# Push_counter.net
KiCad netlist of a schematic drawn in Altium Designer
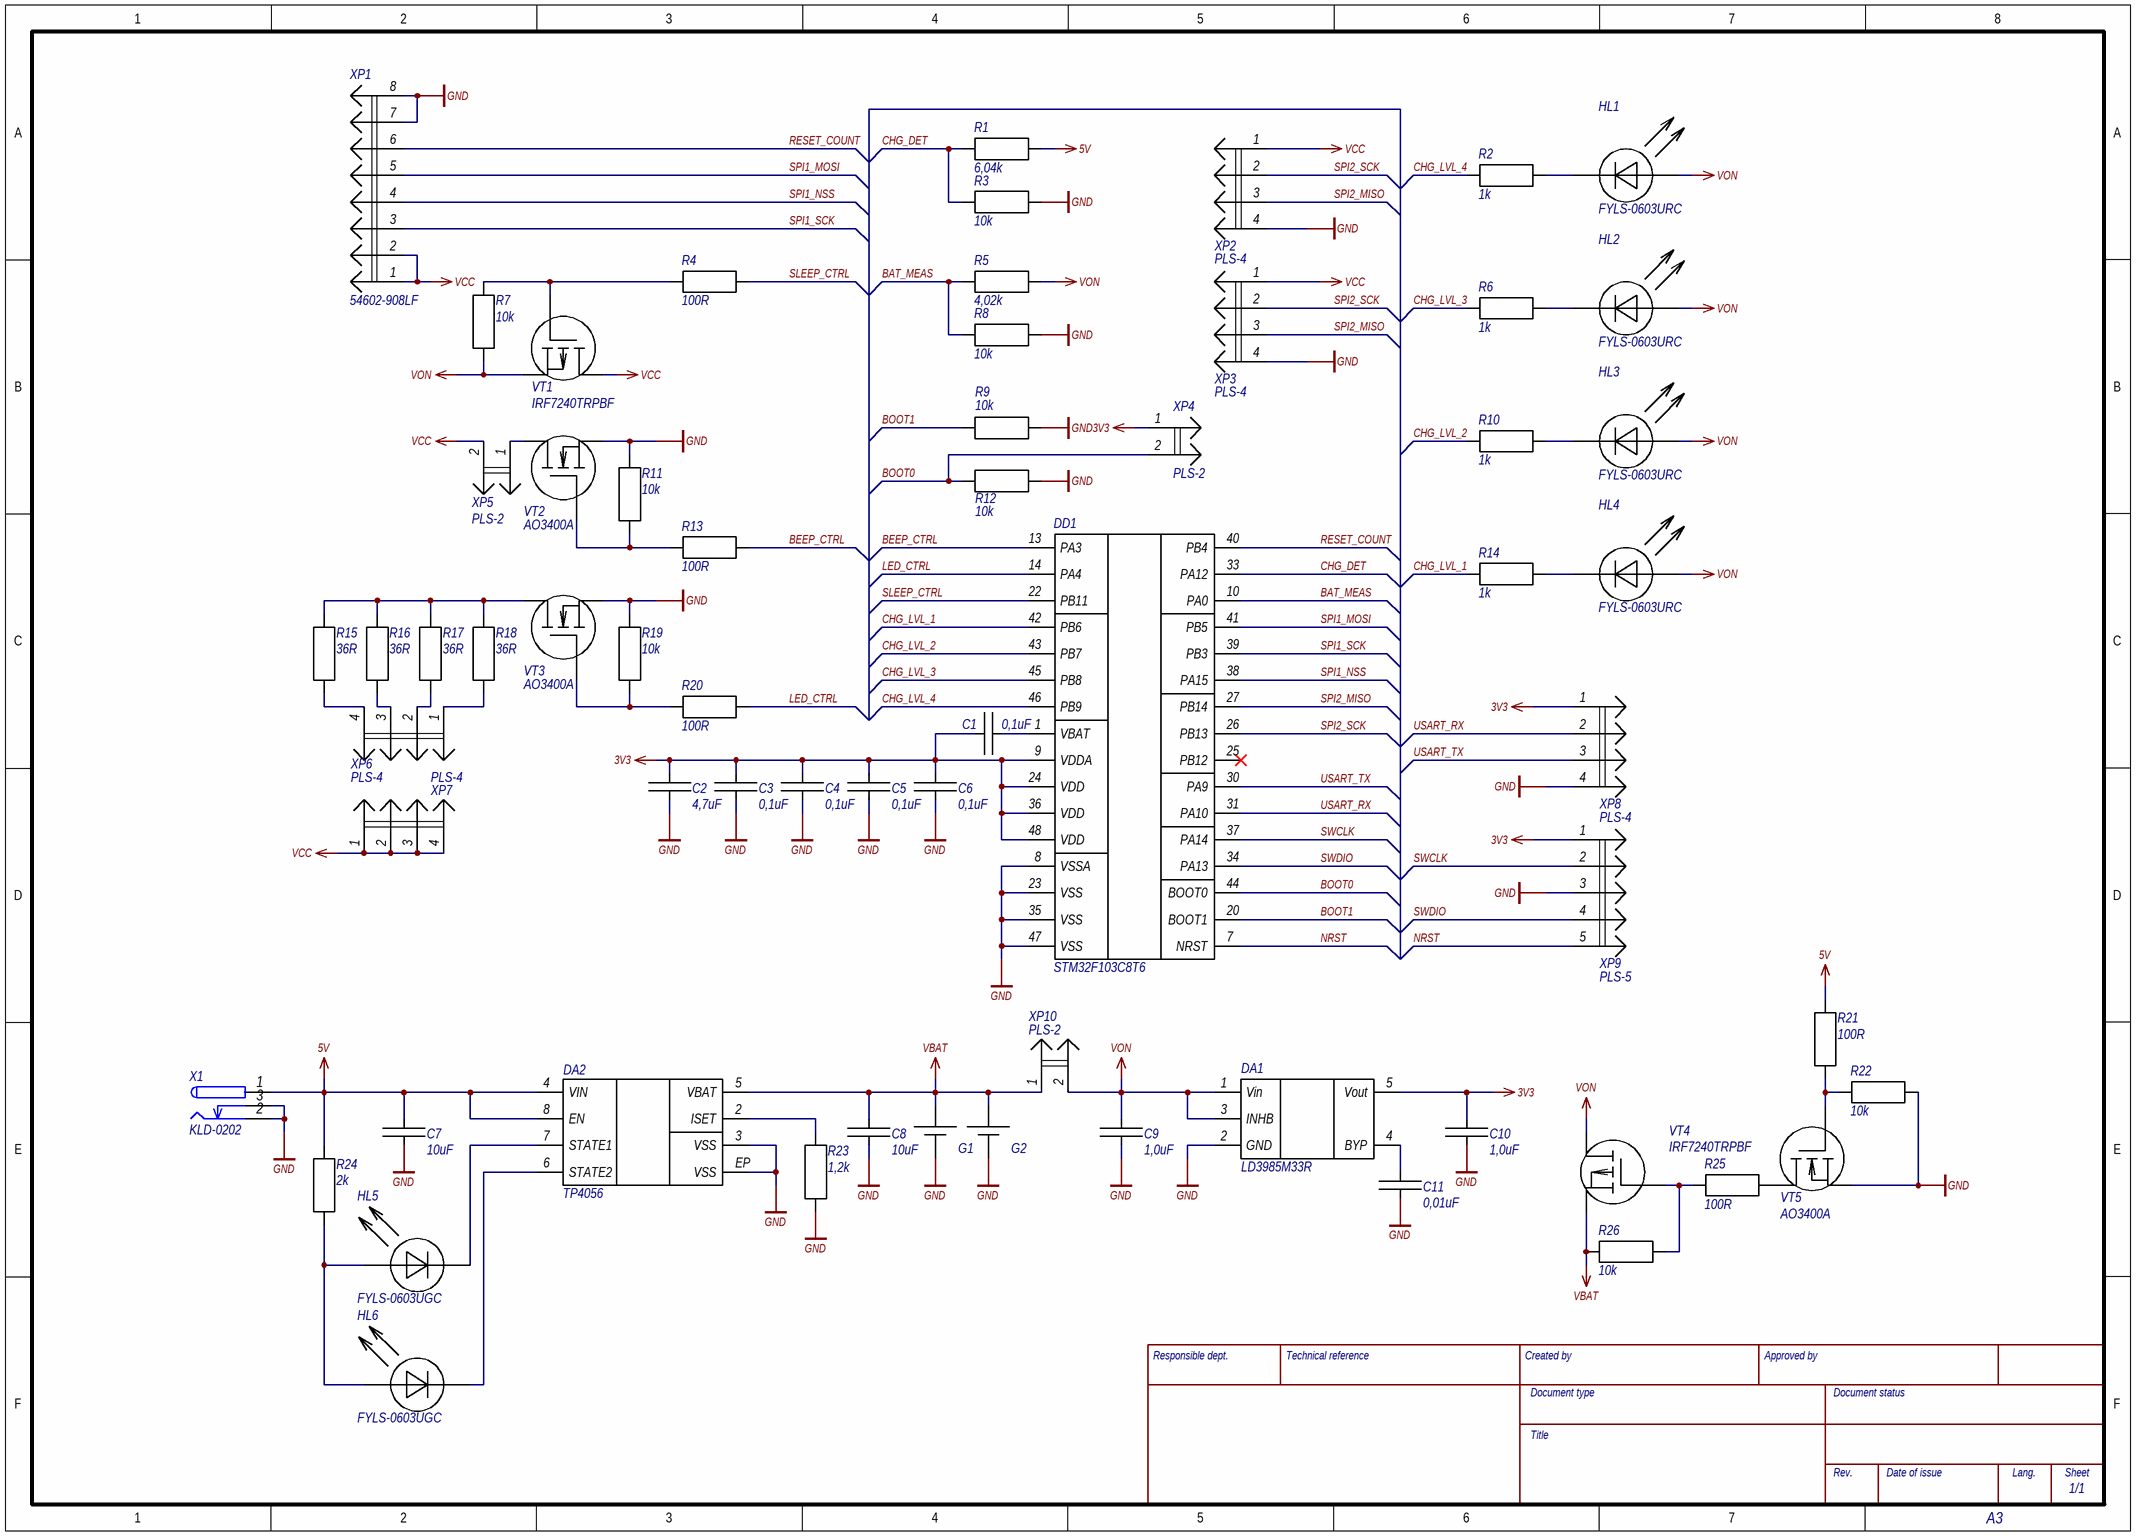
[diagram p0: Push_counter.SchDoc]

(export (version "E")
  (design (tool "Eeschema 10.0.6"))
  (components
    (comp (ref "C1")
      (value "0,1uF")
      (footprint "C0603C")
      (description "C0603C104K5RACAUTO, 0603 X7R  0,1 uF 50V")
      (fields (field (name "PART NUMBER") "C0603C104K5RACAUTO") (field (name "MANUFACTURER") "KEMET"))
      (libsource (lib "lib") (part "Cap"))
    )
    (comp (ref "C2")
      (value "4,7uF")
      (footprint "C0805C")
      (description "CL21B475KOFNFNE, 0805 X7R 4,7 uF 16V")
      (fields (field (name "PART NUMBER") "CL21B475KOFNFNE") (field (name "MANUFACTURER") "Samsung"))
      (libsource (lib "lib") (part "Cap"))
    )
    (comp (ref "C3")
      (value "0,1uF")
      (footprint "C0603C")
      (description "C0603C104K5RACAUTO, 0603 X7R  0,1 uF 50V")
      (fields (field (name "PART NUMBER") "C0603C104K5RACAUTO") (field (name "MANUFACTURER") "KEMET"))
      (libsource (lib "lib") (part "Cap"))
    )
    (comp (ref "C4")
      (value "0,1uF")
      (footprint "C0603C")
      (description "C0603C104K5RACAUTO, 0603 X7R  0,1 uF 50V")
      (fields (field (name "PART NUMBER") "C0603C104K5RACAUTO") (field (name "MANUFACTURER") "KEMET"))
      (libsource (lib "lib") (part "Cap"))
    )
    (comp (ref "C5")
      (value "0,1uF")
      (footprint "C0603C")
      (description "C0603C104K5RACAUTO, 0603 X7R  0,1 uF 50V")
      (fields (field (name "PART NUMBER") "C0603C104K5RACAUTO") (field (name "MANUFACTURER") "KEMET"))
      (libsource (lib "lib") (part "Cap"))
    )
    (comp (ref "C6")
      (value "0,1uF")
      (footprint "C0603C")
      (description "C0603C104K5RACAUTO, 0603 X7R  0,1 uF 50V")
      (fields (field (name "PART NUMBER") "C0603C104K5RACAUTO") (field (name "MANUFACTURER") "KEMET"))
      (libsource (lib "lib") (part "Cap"))
    )
    (comp (ref "C7")
      (value "10uF")
      (footprint "C1210C")
      (description "C3225X7R1H106M250AC, 1210 X7R 10 uF 50V")
      (fields (field (name "PART NUMBER") "C3225X7R1H106M250AC") (field (name "MANUFACTURER") "TDK"))
      (libsource (lib "lib") (part "Cap"))
    )
    (comp (ref "C8")
      (value "10uF")
      (footprint "C1210C")
      (description "C3225X7R1H106M250AC, 1210 X7R 10 uF 50V")
      (fields (field (name "PART NUMBER") "C3225X7R1H106M250AC") (field (name "MANUFACTURER") "TDK"))
      (libsource (lib "lib") (part "Cap"))
    )
    (comp (ref "C9")
      (value "1,0uF")
      (footprint "C0603C")
      (description "CL10B105KA8NNNC, 0603 X7R 1,0 uF 25V")
      (fields (field (name "PART NUMBER") "CL10B105KA8NNNC") (field (name "MANUFACTURER") "Samsung"))
      (libsource (lib "lib") (part "Cap"))
    )
    (comp (ref "C10")
      (value "1,0uF")
      (footprint "C0603C")
      (description "CL10B105KA8NNNC, 0603 X7R 1,0 uF 25V")
      (fields (field (name "PART NUMBER") "CL10B105KA8NNNC") (field (name "MANUFACTURER") "Samsung"))
      (libsource (lib "lib") (part "Cap"))
    )
    (comp (ref "C11")
      (value "0,01uF")
      (footprint "C0603C")
      (description "CL10B103KC8NNNC, 0603 X7R 0,01 uF 100V")
      (fields (field (name "PART NUMBER") "CL10B103KC8NNNC") (field (name "MANUFACTURER") "Samsung"))
      (libsource (lib "lib") (part "Cap"))
    )
    (comp (ref "DA1")
      (value "LD3985M33R")
      (footprint "SOT23-5")
      (description "Linear Voltage Regulator")
      (fields (field (name "MANUFACTURER") "Microchip Technology"))
      (libsource (lib "lib") (part "LD3985M33R"))
    )
    (comp (ref "DA2")
      (value "TP4056")
      (footprint "SO-8-EP")
      (fields (field (name "MANUFACTURER") "UMW"))
      (libsource (lib "lib") (part "TP4056"))
    )
    (comp (ref "DD1")
      (value "STM32F103C8T6")
      (footprint "LQFP48")
      (description "STM32F103C8T6, 64 KB Flash, 20 KB RAM, LQFP48")
      (fields (field (name "MANUFACTURER") "STMicroelectronics"))
      (libsource (lib "lib") (part "STM32F103C8T6"))
    )
    (comp (ref "G1")
      (value "KLS5-18650-L")
      (footprint "KLS5-18650-L")
      (description "KLS5-18650-L, , BAT")
      (libsource (lib "lib") (part "G-ELEM"))
    )
    (comp (ref "G2")
      (value "KLS5-18650-L")
      (footprint "KLS5-18650-L")
      (description "KLS5-18650-L, , BAT")
      (libsource (lib "lib") (part "G-ELEM"))
    )
    (comp (ref "HL1")
      (value "FYLS-0603URC")
      (footprint "LED0603")
      (description "SMD 0603 Red 30mA 80mcd")
      (fields (field (name "MANUFACTURER") "Foryard") (field (name "VOLTAGE") "2.1V"))
      (libsource (lib "lib") (part "LED"))
    )
    (comp (ref "HL2")
      (value "FYLS-0603URC")
      (footprint "LED0603")
      (description "SMD 0603 Red 30mA 80mcd")
      (fields (field (name "MANUFACTURER") "Foryard") (field (name "VOLTAGE") "2.1V"))
      (libsource (lib "lib") (part "LED"))
    )
    (comp (ref "HL3")
      (value "FYLS-0603URC")
      (footprint "LED0603")
      (description "SMD 0603 Red 30mA 80mcd")
      (fields (field (name "MANUFACTURER") "Foryard") (field (name "VOLTAGE") "2.1V"))
      (libsource (lib "lib") (part "LED"))
    )
    (comp (ref "HL4")
      (value "FYLS-0603URC")
      (footprint "LED0603")
      (description "SMD 0603 Red 30mA 80mcd")
      (fields (field (name "MANUFACTURER") "Foryard") (field (name "VOLTAGE") "2.1V"))
      (libsource (lib "lib") (part "LED"))
    )
    (comp (ref "HL5")
      (value "FYLS-0603UGC")
      (footprint "LED0603")
      (description "SMD 0603 Green 30mA 65mcd")
      (fields (field (name "MANUFACTURER") "Foryard") (field (name "VOLTAGE") "2V"))
      (libsource (lib "lib") (part "LED"))
    )
    (comp (ref "HL6")
      (value "FYLS-0603UGC")
      (footprint "LED0603")
      (description "SMD 0603 Green 30mA 65mcd")
      (fields (field (name "MANUFACTURER") "Foryard") (field (name "VOLTAGE") "2V"))
      (libsource (lib "lib") (part "LED"))
    )
    (comp (ref "R1")
      (value "6,04k")
      (footprint "C0603R")
      (description "RC0603FR-076K04L, 1% 6,04k")
      (fields (field (name "PART NUMBER") "RC0603FR-076K04L") (field (name "MANUFACTURER") "Yageo"))
      (libsource (lib "lib") (part "res"))
    )
    (comp (ref "R2")
      (value "1k")
      (footprint "C0603R")
      (description "RC0603JR-071KL, 5% 1k")
      (fields (field (name "PART NUMBER") "RC0603JR-071KL") (field (name "MANUFACTURER") "Yageo"))
      (libsource (lib "lib") (part "res"))
    )
    (comp (ref "R3")
      (value "10k")
      (footprint "C0603R")
      (description "RC0603FR-0710KL, 1% 10k")
      (fields (field (name "PART NUMBER") "RC0603FR-0710KL") (field (name "MANUFACTURER") "Yageo"))
      (libsource (lib "lib") (part "res"))
    )
    (comp (ref "R4")
      (value "100R")
      (footprint "C0603R")
      (description "RC0603FR-07100RL, 1% 100R")
      (fields (field (name "PART NUMBER") "RC0603FR-07100RL") (field (name "MANUFACTURER") "Yageo"))
      (libsource (lib "lib") (part "res"))
    )
    (comp (ref "R5")
      (value "4,02k")
      (footprint "C0603R")
      (description "RC0603FR-074K02L, 1% 4,02k")
      (fields (field (name "PART NUMBER") "RC0603FR-074K02L") (field (name "MANUFACTURER") "Yageo"))
      (libsource (lib "lib") (part "res"))
    )
    (comp (ref "R6")
      (value "1k")
      (footprint "C0603R")
      (description "RC0603JR-071KL, 5% 1k")
      (fields (field (name "PART NUMBER") "RC0603JR-071KL") (field (name "MANUFACTURER") "Yageo"))
      (libsource (lib "lib") (part "res"))
    )
    (comp (ref "R7")
      (value "10k")
      (footprint "C0603R")
      (description "RC0603JR-0710KL, 5% 10k")
      (fields (field (name "PART NUMBER") "RC0603JR-0710KL") (field (name "MANUFACTURER") "Yageo"))
      (libsource (lib "lib") (part "res"))
    )
    (comp (ref "R8")
      (value "10k")
      (footprint "C0603R")
      (description "RC0603FR-0710KL, 1% 10k")
      (fields (field (name "PART NUMBER") "RC0603FR-0710KL") (field (name "MANUFACTURER") "Yageo"))
      (libsource (lib "lib") (part "res"))
    )
    (comp (ref "R9")
      (value "10k")
      (footprint "C0603R")
      (description "RC0603JR-0710KL, 5% 10k")
      (fields (field (name "PART NUMBER") "RC0603JR-0710KL") (field (name "MANUFACTURER") "Yageo"))
      (libsource (lib "lib") (part "res"))
    )
    (comp (ref "R10")
      (value "1k")
      (footprint "C0603R")
      (description "RC0603JR-071KL, 5% 1k")
      (fields (field (name "PART NUMBER") "RC0603JR-071KL") (field (name "MANUFACTURER") "Yageo"))
      (libsource (lib "lib") (part "res"))
    )
    (comp (ref "R11")
      (value "10k")
      (footprint "C0603R")
      (description "RC0603JR-0710KL, 5% 10k")
      (fields (field (name "PART NUMBER") "RC0603JR-0710KL") (field (name "MANUFACTURER") "Yageo"))
      (libsource (lib "lib") (part "res"))
    )
    (comp (ref "R12")
      (value "10k")
      (footprint "C0603R")
      (description "RC0603JR-0710KL, 5% 10k")
      (fields (field (name "PART NUMBER") "RC0603JR-0710KL") (field (name "MANUFACTURER") "Yageo"))
      (libsource (lib "lib") (part "res"))
    )
    (comp (ref "R13")
      (value "100R")
      (footprint "C0603R")
      (description "RC0603FR-07100RL, 1% 100R")
      (fields (field (name "PART NUMBER") "RC0603FR-07100RL") (field (name "MANUFACTURER") "Yageo"))
      (libsource (lib "lib") (part "res"))
    )
    (comp (ref "R14")
      (value "1k")
      (footprint "C0603R")
      (description "RC0603JR-071KL, 5% 1k")
      (fields (field (name "PART NUMBER") "RC0603JR-071KL") (field (name "MANUFACTURER") "Yageo"))
      (libsource (lib "lib") (part "res"))
    )
    (comp (ref "R15")
      (value "36R")
      (footprint "C1206R")
      (description "RC1206JR-0736RL, 5% 36R")
      (fields (field (name "PART NUMBER") "RC1206JR-0736RL") (field (name "MANUFACTURER") "Yageo"))
      (libsource (lib "lib") (part "res"))
    )
    (comp (ref "R16")
      (value "36R")
      (footprint "C1206R")
      (description "RC1206JR-0736RL, 5% 36R")
      (fields (field (name "PART NUMBER") "RC1206JR-0736RL") (field (name "MANUFACTURER") "Yageo"))
      (libsource (lib "lib") (part "res"))
    )
    (comp (ref "R17")
      (value "36R")
      (footprint "C1206R")
      (description "RC1206JR-0736RL, 5% 36R")
      (fields (field (name "PART NUMBER") "RC1206JR-0736RL") (field (name "MANUFACTURER") "Yageo"))
      (libsource (lib "lib") (part "res"))
    )
    (comp (ref "R18")
      (value "36R")
      (footprint "C1206R")
      (description "RC1206JR-0736RL, 5% 36R")
      (fields (field (name "PART NUMBER") "RC1206JR-0736RL") (field (name "MANUFACTURER") "Yageo"))
      (libsource (lib "lib") (part "res"))
    )
    (comp (ref "R19")
      (value "10k")
      (footprint "C0603R")
      (description "RC0603JR-0710KL, 5% 10k")
      (fields (field (name "PART NUMBER") "RC0603JR-0710KL") (field (name "MANUFACTURER") "Yageo"))
      (libsource (lib "lib") (part "res"))
    )
    (comp (ref "R20")
      (value "100R")
      (footprint "C0603R")
      (description "RC0603FR-07100RL, 1% 100R")
      (fields (field (name "PART NUMBER") "RC0603FR-07100RL") (field (name "MANUFACTURER") "Yageo"))
      (libsource (lib "lib") (part "res"))
    )
    (comp (ref "R21")
      (value "100R")
      (footprint "C0603R")
      (description "RC0603FR-07100RL, 1% 100R")
      (fields (field (name "PART NUMBER") "RC0603FR-07100RL") (field (name "MANUFACTURER") "Yageo"))
      (libsource (lib "lib") (part "res"))
    )
    (comp (ref "R22")
      (value "10k")
      (footprint "C0603R")
      (description "RC0603JR-0710KL, 5% 10k")
      (fields (field (name "PART NUMBER") "RC0603JR-0710KL") (field (name "MANUFACTURER") "Yageo"))
      (libsource (lib "lib") (part "res"))
    )
    (comp (ref "R23")
      (value "1,2k")
      (footprint "C0603R")
      (description "RC0603JR-071K2L, 5% 1,2k")
      (fields (field (name "PART NUMBER") "RC0603JR-071K2L") (field (name "MANUFACTURER") "Yageo"))
      (libsource (lib "lib") (part "res"))
    )
    (comp (ref "R24")
      (value "2k")
      (footprint "C0603R")
      (description "RC0603JR-072KL, 5% 2k")
      (fields (field (name "PART NUMBER") "RC0603JR-072KL") (field (name "MANUFACTURER") "Yageo"))
      (libsource (lib "lib") (part "res"))
    )
    (comp (ref "R25")
      (value "100R")
      (footprint "C0603R")
      (description "RC0603FR-07100RL, 1% 100R")
      (fields (field (name "PART NUMBER") "RC0603FR-07100RL") (field (name "MANUFACTURER") "Yageo"))
      (libsource (lib "lib") (part "res"))
    )
    (comp (ref "R26")
      (value "10k")
      (footprint "C0603R")
      (description "RC0603JR-0710KL, 5% 10k")
      (fields (field (name "PART NUMBER") "RC0603JR-0710KL") (field (name "MANUFACTURER") "Yageo"))
      (libsource (lib "lib") (part "res"))
    )
    (comp (ref "VT1")
      (value "IRF7240TRPBF")
      (footprint "SO-8-SINGLE-FET")
      (description "IRF7240TRPBF, SO-8 A V")
      (fields (field (name "MANUFACTURER") "Infineon"))
      (libsource (lib "lib") (part "TRANS-P-FET"))
    )
    (comp (ref "VT2")
      (value "AO3400A")
      (footprint "SOT23-3-FET")
      (description "AO3400A, SOT23-3 5A 30V")
      (fields (field (name "MANUFACTURER") "UMW"))
      (libsource (lib "lib") (part "TRANS-N-FET"))
    )
    (comp (ref "VT3")
      (value "AO3400A")
      (footprint "SOT23-3-FET")
      (description "AO3400A, SOT23-3 5A 30V")
      (fields (field (name "MANUFACTURER") "UMW"))
      (libsource (lib "lib") (part "TRANS-N-FET"))
    )
    (comp (ref "VT4")
      (value "IRF7240TRPBF")
      (footprint "SO-8-SINGLE-FET")
      (description "IRF7240TRPBF, SO-8 A V")
      (fields (field (name "MANUFACTURER") "Infineon"))
      (libsource (lib "lib") (part "TRANS-P-FET"))
    )
    (comp (ref "VT5")
      (value "AO3400A")
      (footprint "SOT23-3-FET")
      (description "AO3400A, SOT23-3 5A 30V")
      (fields (field (name "MANUFACTURER") "UMW"))
      (libsource (lib "lib") (part "TRANS-N-FET"))
    )
    (comp (ref "X1")
      (value "KLD-0202")
      (footprint "KLD-0202")
      (description "KLD-0202, Kycon,")
      (fields (field (name "MANUFACTURER") "Kycon"))
      (libsource (lib "lib") (part "PWR2.5"))
    )
    (comp (ref "XP1")
      (value "54602-908LF")
      (footprint "54602-908LF")
      (description "54602-908LF, , ETH")
      (libsource (lib "lib") (part "Connector-8"))
    )
    (comp (ref "XP2")
      (value "PLS-4")
      (footprint "PLS-4")
      (description "PLS-4, , PLS 4 Pins")
      (libsource (lib "lib") (part "Connector-4"))
    )
    (comp (ref "XP3")
      (value "PLS-4")
      (footprint "PLS-4")
      (description "PLS-4, , PLS 4 Pins")
      (libsource (lib "lib") (part "Connector-4"))
    )
    (comp (ref "XP4")
      (value "PLS-2")
      (footprint "PLS-2")
      (description "PLS-2, , PLS 2 Pins")
      (libsource (lib "lib") (part "Connector-2"))
    )
    (comp (ref "XP5")
      (value "PLS-2")
      (footprint "PLS-2")
      (description "PLS-2, , PLS 2 Pins")
      (libsource (lib "lib") (part "Connector-2"))
    )
    (comp (ref "XP6")
      (value "PLS-4")
      (footprint "PLS-4")
      (description "PLS-4, , PLS 4 Pins")
      (libsource (lib "lib") (part "Connector-4"))
    )
    (comp (ref "XP7")
      (value "PLS-4")
      (footprint "PLS-4")
      (description "PLS-4, , PLS 4 Pins")
      (libsource (lib "lib") (part "Connector-4"))
    )
    (comp (ref "XP8")
      (value "PLS-4")
      (footprint "PLS-4")
      (description "PLS-4, , PLS 4 Pins")
      (libsource (lib "lib") (part "Connector-4"))
    )
    (comp (ref "XP9")
      (value "PLS-5")
      (footprint "PLS-5")
      (description "PLS-5, , PLS 5 Pins")
      (libsource (lib "lib") (part "Connector-5"))
    )
    (comp (ref "XP10")
      (value "PLS-2")
      (footprint "PLS-2")
      (description "PLS-2, , PLS 2 Pins")
      (libsource (lib "lib") (part "Connector-2"))
    )
  )
  (nets
    (net (code "1") (name "/BAT_MEAS") (class "Default")
      (node (ref "DD1") (pin "10") (pinfunction "PA0_10") (pintype "passive"))
      (node (ref "R5") (pin "2") (pinfunction "2_2") (pintype "passive"))
      (node (ref "R8") (pin "2") (pinfunction "2_2") (pintype "passive"))
    )
    (net (code "2") (name "/BEEP_CTRL") (class "Default")
      (node (ref "DD1") (pin "13") (pinfunction "PA3_13") (pintype "passive"))
      (node (ref "R13") (pin "1") (pinfunction "1_1") (pintype "passive"))
    )
    (net (code "3") (name "/BOOT0") (class "Default")
      (node (ref "DD1") (pin "44") (pinfunction "BOOT0_44") (pintype "passive"))
      (node (ref "R12") (pin "2") (pinfunction "2_2") (pintype "passive"))
      (node (ref "XP4") (pin "2") (pinfunction "2_2") (pintype "passive"))
    )
    (net (code "4") (name "/BOOT1") (class "Default")
      (node (ref "DD1") (pin "20") (pinfunction "BOOT1_20") (pintype "passive"))
      (node (ref "R9") (pin "2") (pinfunction "2_2") (pintype "passive"))
    )
    (net (code "5") (name "/CHG_DET") (class "Default")
      (node (ref "DD1") (pin "33") (pinfunction "PA12_33") (pintype "passive"))
      (node (ref "R1") (pin "2") (pinfunction "2_2") (pintype "passive"))
      (node (ref "R3") (pin "2") (pinfunction "2_2") (pintype "passive"))
    )
    (net (code "6") (name "/CHG_LVL_1") (class "Default")
      (node (ref "DD1") (pin "42") (pinfunction "PB6_42") (pintype "passive"))
      (node (ref "R14") (pin "2") (pinfunction "2_2") (pintype "passive"))
    )
    (net (code "7") (name "/CHG_LVL_2") (class "Default")
      (node (ref "DD1") (pin "43") (pinfunction "PB7_43") (pintype "passive"))
      (node (ref "R10") (pin "2") (pinfunction "2_2") (pintype "passive"))
    )
    (net (code "8") (name "/CHG_LVL_3") (class "Default")
      (node (ref "DD1") (pin "45") (pinfunction "PB8_45") (pintype "passive"))
      (node (ref "R6") (pin "2") (pinfunction "2_2") (pintype "passive"))
    )
    (net (code "9") (name "/CHG_LVL_4") (class "Default")
      (node (ref "DD1") (pin "46") (pinfunction "PB9_46") (pintype "passive"))
      (node (ref "R2") (pin "2") (pinfunction "2_2") (pintype "passive"))
    )
    (net (code "10") (name "/LED_CTRL") (class "Default")
      (node (ref "DD1") (pin "14") (pinfunction "PA4_14") (pintype "passive"))
      (node (ref "R20") (pin "1") (pinfunction "1_1") (pintype "passive"))
    )
    (net (code "11") (name "/NRST") (class "Default")
      (node (ref "DD1") (pin "7") (pinfunction "NRST_7") (pintype "passive"))
      (node (ref "XP9") (pin "5") (pinfunction "5_5") (pintype "passive"))
    )
    (net (code "12") (name "/RESET_COUNT") (class "Default")
      (node (ref "DD1") (pin "40") (pinfunction "PB4_40") (pintype "passive"))
      (node (ref "XP1") (pin "6") (pinfunction "6_6") (pintype "passive"))
    )
    (net (code "13") (name "/SLEEP_CTRL") (class "Default")
      (node (ref "DD1") (pin "22") (pinfunction "PB11_22") (pintype "passive"))
      (node (ref "R4") (pin "1") (pinfunction "1_1") (pintype "passive"))
    )
    (net (code "14") (name "/SPI1_MOSI") (class "Default")
      (node (ref "DD1") (pin "41") (pinfunction "PB5_41") (pintype "passive"))
      (node (ref "XP1") (pin "5") (pinfunction "5_5") (pintype "passive"))
    )
    (net (code "15") (name "/SPI1_NSS") (class "Default")
      (node (ref "DD1") (pin "38") (pinfunction "PA15_38") (pintype "passive"))
      (node (ref "XP1") (pin "4") (pinfunction "4_4") (pintype "passive"))
    )
    (net (code "16") (name "/SPI1_SCK") (class "Default")
      (node (ref "DD1") (pin "39") (pinfunction "PB3_39") (pintype "passive"))
      (node (ref "XP1") (pin "3") (pinfunction "3_3") (pintype "passive"))
    )
    (net (code "17") (name "/SPI2_MISO") (class "Default")
      (node (ref "DD1") (pin "27") (pinfunction "PB14_27") (pintype "passive"))
      (node (ref "XP2") (pin "3") (pinfunction "3_3") (pintype "passive"))
      (node (ref "XP3") (pin "3") (pinfunction "3_3") (pintype "passive"))
    )
    (net (code "18") (name "/SPI2_SCK") (class "Default")
      (node (ref "DD1") (pin "26") (pinfunction "PB13_26") (pintype "passive"))
      (node (ref "XP2") (pin "2") (pinfunction "2_2") (pintype "passive"))
      (node (ref "XP3") (pin "2") (pinfunction "2_2") (pintype "passive"))
    )
    (net (code "19") (name "/SWCLK") (class "Default")
      (node (ref "DD1") (pin "37") (pinfunction "PA14_37") (pintype "passive"))
      (node (ref "XP9") (pin "2") (pinfunction "2_2") (pintype "passive"))
    )
    (net (code "20") (name "/SWDIO") (class "Default")
      (node (ref "DD1") (pin "34") (pinfunction "PA13_34") (pintype "passive"))
      (node (ref "XP9") (pin "4") (pinfunction "4_4") (pintype "passive"))
    )
    (net (code "21") (name "/USART_RX") (class "Default")
      (node (ref "DD1") (pin "31") (pinfunction "PA10_31") (pintype "passive"))
      (node (ref "XP8") (pin "2") (pinfunction "2_2") (pintype "passive"))
    )
    (net (code "22") (name "/USART_TX") (class "Default")
      (node (ref "DD1") (pin "30") (pinfunction "PA9_30") (pintype "passive"))
      (node (ref "XP8") (pin "3") (pinfunction "3_3") (pintype "passive"))
    )
    (net (code "23") (name "3V3") (class "Default")
      (node (ref "C1") (pin "1") (pinfunction "1_1") (pintype "passive"))
      (node (ref "C10") (pin "1") (pinfunction "1_1") (pintype "passive"))
      (node (ref "C2") (pin "1") (pinfunction "1_1") (pintype "passive"))
      (node (ref "C3") (pin "1") (pinfunction "1_1") (pintype "passive"))
      (node (ref "C4") (pin "1") (pinfunction "1_1") (pintype "passive"))
      (node (ref "C5") (pin "1") (pinfunction "1_1") (pintype "passive"))
      (node (ref "C6") (pin "1") (pinfunction "1_1") (pintype "passive"))
      (node (ref "DA1") (pin "5") (pinfunction "Vout_5") (pintype "passive"))
      (node (ref "DD1") (pin "24") (pinfunction "VDD_24") (pintype "passive"))
      (node (ref "DD1") (pin "36") (pinfunction "VDD_36") (pintype "passive"))
      (node (ref "DD1") (pin "48") (pinfunction "VDD_48") (pintype "passive"))
      (node (ref "DD1") (pin "9") (pinfunction "VDDA_9") (pintype "passive"))
      (node (ref "XP4") (pin "1") (pinfunction "1_1") (pintype "passive"))
      (node (ref "XP8") (pin "1") (pinfunction "1_1") (pintype "passive"))
      (node (ref "XP9") (pin "1") (pinfunction "1_1") (pintype "passive"))
    )
    (net (code "24") (name "5V") (class "Default")
      (node (ref "C7") (pin "1") (pinfunction "1_1") (pintype "passive"))
      (node (ref "DA2") (pin "4") (pinfunction "VIN_4") (pintype "passive"))
      (node (ref "DA2") (pin "8") (pinfunction "EN_8") (pintype "passive"))
      (node (ref "R1") (pin "1") (pinfunction "1_1") (pintype "passive"))
      (node (ref "R21") (pin "1") (pinfunction "1_1") (pintype "passive"))
      (node (ref "R24") (pin "1") (pinfunction "1_1") (pintype "passive"))
      (node (ref "X1") (pin "1") (pinfunction "1_1") (pintype "power_in"))
    )
    (net (code "25") (name "GND") (class "Default")
      (node (ref "C10") (pin "2") (pinfunction "2_2") (pintype "passive"))
      (node (ref "C11") (pin "2") (pinfunction "2_2") (pintype "passive"))
      (node (ref "C2") (pin "2") (pinfunction "2_2") (pintype "passive"))
      (node (ref "C3") (pin "2") (pinfunction "2_2") (pintype "passive"))
      (node (ref "C4") (pin "2") (pinfunction "2_2") (pintype "passive"))
      (node (ref "C5") (pin "2") (pinfunction "2_2") (pintype "passive"))
      (node (ref "C6") (pin "2") (pinfunction "2_2") (pintype "passive"))
      (node (ref "C7") (pin "2") (pinfunction "2_2") (pintype "passive"))
      (node (ref "C8") (pin "2") (pinfunction "2_2") (pintype "passive"))
      (node (ref "C9") (pin "2") (pinfunction "2_2") (pintype "passive"))
      (node (ref "DA1") (pin "2") (pinfunction "GND_2") (pintype "passive"))
      (node (ref "DA2") (pin "3") (pinfunction "VSS_3") (pintype "passive"))
      (node (ref "DA2") (pin "EP") (pinfunction "VSS_EP") (pintype "passive"))
      (node (ref "DD1") (pin "23") (pinfunction "VSS_23") (pintype "passive"))
      (node (ref "DD1") (pin "35") (pinfunction "VSS_35") (pintype "passive"))
      (node (ref "DD1") (pin "47") (pinfunction "VSS_47") (pintype "passive"))
      (node (ref "DD1") (pin "8") (pinfunction "VSSA_8") (pintype "passive"))
      (node (ref "G1") (pin "1") (pinfunction "-_1") (pintype "passive"))
      (node (ref "G2") (pin "1") (pinfunction "-_1") (pintype "passive"))
      (node (ref "R11") (pin "1") (pinfunction "1_1") (pintype "passive"))
      (node (ref "R12") (pin "1") (pinfunction "1_1") (pintype "passive"))
      (node (ref "R19") (pin "1") (pinfunction "1_1") (pintype "passive"))
      (node (ref "R22") (pin "2") (pinfunction "2_2") (pintype "passive"))
      (node (ref "R23") (pin "2") (pinfunction "2_2") (pintype "passive"))
      (node (ref "R3") (pin "1") (pinfunction "1_1") (pintype "passive"))
      (node (ref "R8") (pin "1") (pinfunction "1_1") (pintype "passive"))
      (node (ref "R9") (pin "1") (pinfunction "1_1") (pintype "passive"))
      (node (ref "VT2") (pin "S") (pinfunction "S_S") (pintype "passive"))
      (node (ref "VT3") (pin "S") (pinfunction "S_S") (pintype "passive"))
      (node (ref "VT5") (pin "S") (pinfunction "S_S") (pintype "passive"))
      (node (ref "X1") (pin "2") (pinfunction "2_2") (pintype "power_in"))
      (node (ref "X1") (pin "3") (pinfunction "3_3") (pintype "power_in"))
      (node (ref "XP1") (pin "7") (pinfunction "7_7") (pintype "passive"))
      (node (ref "XP1") (pin "8") (pinfunction "8_8") (pintype "passive"))
      (node (ref "XP2") (pin "4") (pinfunction "4_4") (pintype "passive"))
      (node (ref "XP3") (pin "4") (pinfunction "4_4") (pintype "passive"))
      (node (ref "XP8") (pin "4") (pinfunction "4_4") (pintype "passive"))
      (node (ref "XP9") (pin "3") (pinfunction "3_3") (pintype "passive"))
    )
    (net (code "26") (name "Net-(DA1-BYP)") (class "Default")
      (node (ref "C11") (pin "1") (pinfunction "1_1") (pintype "passive"))
      (node (ref "DA1") (pin "4") (pinfunction "BYP_4") (pintype "passive"))
    )
    (net (code "27") (name "Net-(DA2-ISET)") (class "Default")
      (node (ref "DA2") (pin "2") (pinfunction "ISET_2") (pintype "passive"))
      (node (ref "R23") (pin "1") (pinfunction "1_1") (pintype "passive"))
    )
    (net (code "28") (name "Net-(DA2-STATE1)") (class "Default")
      (node (ref "DA2") (pin "7") (pinfunction "STATE1_7") (pintype "passive"))
      (node (ref "HL5") (pin "2") (pinfunction "C_2") (pintype "passive"))
    )
    (net (code "29") (name "Net-(DA2-STATE2)") (class "Default")
      (node (ref "DA2") (pin "6") (pinfunction "STATE2_6") (pintype "passive"))
      (node (ref "HL6") (pin "2") (pinfunction "C_2") (pintype "passive"))
    )
    (net (code "30") (name "Net-(DD1-VBAT)") (class "Default")
      (node (ref "C1") (pin "2") (pinfunction "2_2") (pintype "passive"))
      (node (ref "DD1") (pin "1") (pinfunction "VBAT_1") (pintype "passive"))
    )
    (net (code "31") (name "Net-(HL1-C)") (class "Default")
      (node (ref "HL1") (pin "2") (pinfunction "C_2") (pintype "passive"))
      (node (ref "R2") (pin "1") (pinfunction "1_1") (pintype "passive"))
    )
    (net (code "32") (name "Net-(HL2-C)") (class "Default")
      (node (ref "HL2") (pin "2") (pinfunction "C_2") (pintype "passive"))
      (node (ref "R6") (pin "1") (pinfunction "1_1") (pintype "passive"))
    )
    (net (code "33") (name "Net-(HL3-C)") (class "Default")
      (node (ref "HL3") (pin "2") (pinfunction "C_2") (pintype "passive"))
      (node (ref "R10") (pin "1") (pinfunction "1_1") (pintype "passive"))
    )
    (net (code "34") (name "Net-(HL4-C)") (class "Default")
      (node (ref "HL4") (pin "2") (pinfunction "C_2") (pintype "passive"))
      (node (ref "R14") (pin "1") (pinfunction "1_1") (pintype "passive"))
    )
    (net (code "35") (name "Net-(HL5-A)") (class "Default")
      (node (ref "HL5") (pin "1") (pinfunction "A_1") (pintype "passive"))
      (node (ref "HL6") (pin "1") (pinfunction "A_1") (pintype "passive"))
      (node (ref "R24") (pin "2") (pinfunction "2_2") (pintype "passive"))
    )
    (net (code "36") (name "Net-(R4-Pad2)") (class "Default")
      (node (ref "R4") (pin "2") (pinfunction "2_2") (pintype "passive"))
      (node (ref "R7") (pin "2") (pinfunction "2_2") (pintype "passive"))
      (node (ref "VT1") (pin "G") (pinfunction "G_G") (pintype "passive"))
    )
    (net (code "37") (name "Net-(R11-Pad2)") (class "Default")
      (node (ref "R11") (pin "2") (pinfunction "2_2") (pintype "passive"))
      (node (ref "R13") (pin "2") (pinfunction "2_2") (pintype "passive"))
      (node (ref "VT2") (pin "G") (pinfunction "G_G") (pintype "passive"))
    )
    (net (code "38") (name "Net-(R15-Pad1)") (class "Default")
      (node (ref "R15") (pin "1") (pinfunction "1_1") (pintype "passive"))
      (node (ref "R16") (pin "1") (pinfunction "1_1") (pintype "passive"))
      (node (ref "R17") (pin "1") (pinfunction "1_1") (pintype "passive"))
      (node (ref "R18") (pin "1") (pinfunction "1_1") (pintype "passive"))
      (node (ref "VT3") (pin "D") (pinfunction "D_D") (pintype "passive"))
    )
    (net (code "39") (name "Net-(R15-Pad2)") (class "Default")
      (node (ref "R15") (pin "2") (pinfunction "2_2") (pintype "passive"))
      (node (ref "XP6") (pin "4") (pinfunction "4_4") (pintype "passive"))
    )
    (net (code "40") (name "Net-(R16-Pad2)") (class "Default")
      (node (ref "R16") (pin "2") (pinfunction "2_2") (pintype "passive"))
      (node (ref "XP6") (pin "3") (pinfunction "3_3") (pintype "passive"))
    )
    (net (code "41") (name "Net-(R17-Pad2)") (class "Default")
      (node (ref "R17") (pin "2") (pinfunction "2_2") (pintype "passive"))
      (node (ref "XP6") (pin "2") (pinfunction "2_2") (pintype "passive"))
    )
    (net (code "42") (name "Net-(R18-Pad2)") (class "Default")
      (node (ref "R18") (pin "2") (pinfunction "2_2") (pintype "passive"))
      (node (ref "XP6") (pin "1") (pinfunction "1_1") (pintype "passive"))
    )
    (net (code "43") (name "Net-(R19-Pad2)") (class "Default")
      (node (ref "R19") (pin "2") (pinfunction "2_2") (pintype "passive"))
      (node (ref "R20") (pin "2") (pinfunction "2_2") (pintype "passive"))
      (node (ref "VT3") (pin "G") (pinfunction "G_G") (pintype "passive"))
    )
    (net (code "44") (name "Net-(R21-Pad2)") (class "Default")
      (node (ref "R21") (pin "2") (pinfunction "2_2") (pintype "passive"))
      (node (ref "R22") (pin "1") (pinfunction "1_1") (pintype "passive"))
      (node (ref "VT5") (pin "G") (pinfunction "G_G") (pintype "passive"))
    )
    (net (code "45") (name "Net-(R25-Pad1)") (class "Default")
      (node (ref "R25") (pin "1") (pinfunction "1_1") (pintype "passive"))
      (node (ref "R26") (pin "2") (pinfunction "2_2") (pintype "passive"))
      (node (ref "VT4") (pin "G") (pinfunction "G_G") (pintype "passive"))
    )
    (net (code "46") (name "Net-(R25-Pad2)") (class "Default")
      (node (ref "R25") (pin "2") (pinfunction "2_2") (pintype "passive"))
      (node (ref "VT5") (pin "D") (pinfunction "D_D") (pintype "passive"))
    )
    (net (code "47") (name "Net-(VT2-PadD)") (class "Default")
      (node (ref "VT2") (pin "D") (pinfunction "D_D") (pintype "passive"))
      (node (ref "XP5") (pin "1") (pinfunction "1_1") (pintype "passive"))
    )
    (net (code "48") (name "VBAT") (class "Default")
      (node (ref "C8") (pin "1") (pinfunction "1_1") (pintype "passive"))
      (node (ref "DA2") (pin "5") (pinfunction "VBAT_5") (pintype "passive"))
      (node (ref "G1") (pin "2") (pinfunction "+_2") (pintype "passive"))
      (node (ref "G2") (pin "2") (pinfunction "+_2") (pintype "passive"))
      (node (ref "R26") (pin "1") (pinfunction "1_1") (pintype "passive"))
      (node (ref "VT4") (pin "S") (pinfunction "S_S") (pintype "passive"))
      (node (ref "XP10") (pin "1") (pinfunction "1_1") (pintype "passive"))
    )
    (net (code "49") (name "VCC") (class "Default")
      (node (ref "VT1") (pin "D") (pinfunction "D_D") (pintype "passive"))
      (node (ref "XP1") (pin "1") (pinfunction "1_1") (pintype "passive"))
      (node (ref "XP1") (pin "2") (pinfunction "2_2") (pintype "passive"))
      (node (ref "XP2") (pin "1") (pinfunction "1_1") (pintype "passive"))
      (node (ref "XP3") (pin "1") (pinfunction "1_1") (pintype "passive"))
      (node (ref "XP5") (pin "2") (pinfunction "2_2") (pintype "passive"))
      (node (ref "XP7") (pin "1") (pinfunction "1_1") (pintype "passive"))
      (node (ref "XP7") (pin "2") (pinfunction "2_2") (pintype "passive"))
      (node (ref "XP7") (pin "3") (pinfunction "3_3") (pintype "passive"))
      (node (ref "XP7") (pin "4") (pinfunction "4_4") (pintype "passive"))
    )
    (net (code "50") (name "VON") (class "Default")
      (node (ref "C9") (pin "1") (pinfunction "1_1") (pintype "passive"))
      (node (ref "DA1") (pin "1") (pinfunction "Vin_1") (pintype "passive"))
      (node (ref "DA1") (pin "3") (pinfunction "INHB_3") (pintype "passive"))
      (node (ref "HL1") (pin "1") (pinfunction "A_1") (pintype "passive"))
      (node (ref "HL2") (pin "1") (pinfunction "A_1") (pintype "passive"))
      (node (ref "HL3") (pin "1") (pinfunction "A_1") (pintype "passive"))
      (node (ref "HL4") (pin "1") (pinfunction "A_1") (pintype "passive"))
      (node (ref "R5") (pin "1") (pinfunction "1_1") (pintype "passive"))
      (node (ref "R7") (pin "1") (pinfunction "1_1") (pintype "passive"))
      (node (ref "VT1") (pin "S") (pinfunction "S_S") (pintype "passive"))
      (node (ref "VT4") (pin "D") (pinfunction "D_D") (pintype "passive"))
      (node (ref "XP10") (pin "2") (pinfunction "2_2") (pintype "passive"))
    )
    (net (code "51") (name "unconnected-(DD1-PB12-Pad25)") (class "Default")
      (node (ref "DD1") (pin "25") (pinfunction "PB12_25") (pintype "passive+no_connect"))
    )
  )
)
